# SCH_TEMT6000.net
KiCad netlist of a schematic drawn in Altium Designer
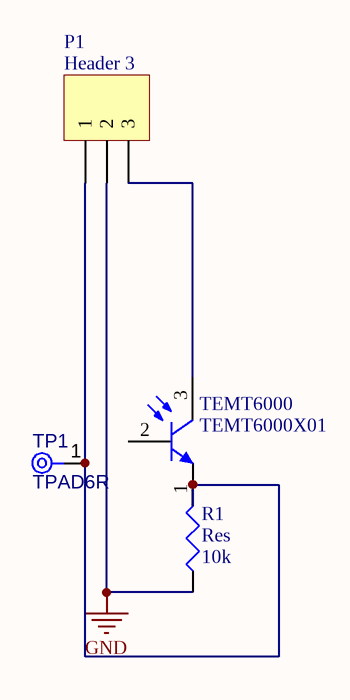
[diagram p0: SCH_TEMT6000.SchDoc]

(export (version "E")
  (design (tool "Eeschema 10.0.6"))
  (components
    (comp (ref "P1")
      (value "Header 3")
      (footprint "HDR1X3")
      (description "Header, 3-Pin")
      (fields (field (name "PUBLISHER") "Altium Limited"))
      (libsource (lib "Miscellaneous Connectors") (part "Header 3"))
    )
    (comp (ref "R1")
      (value "Res")
      (footprint "J1-0603")
      (description "Resistor")
      (fields (field (name "ALTIUM_VALUE") "10k") (field (name "PUBLISHER") "Altium Limited"))
      (libsource (lib "Miscellaneous Devices") (part "Res3"))
    )
    (comp (ref "TEMT6000")
      (value "TEMT6000X01")
      (footprint "VSIL-TEMT6000X01_V")
      (description "Ambient Light Sensor, 100 mW, -40 to 100 degC, 3-Pin SMD, RoHS, Tape and Reel")
      (fields (field (name "MANUFACTURER") "Vishay Siliconix"))
      (libsource (lib "Titouan Lasquellec") (part "PHOTO-NPN-EBC-3"))
    )
    (comp (ref "TP1")
      (value "TPAD6R")
      (footprint "TP06R")
      (description "0.6mm round")
      (libsource (lib "Titouan Lasquellec") (part "CMP-001-0001-4"))
    )
  )
  (nets
    (net (code "1") (name "GND") (class "Default")
      (node (ref "P1") (pin "2") (pinfunction "2_2") (pintype "passive"))
      (node (ref "R1") (pin "1") (pinfunction "1_1") (pintype "passive"))
    )
    (net (code "2") (name "Net-(TEMT6000-C)") (class "Default")
      (node (ref "P1") (pin "3") (pinfunction "3_3") (pintype "passive"))
      (node (ref "TEMT6000") (pin "3") (pinfunction "C_3") (pintype "passive"))
    )
    (net (code "3") (name "Net-(TEMT6000-E)") (class "Default")
      (node (ref "P1") (pin "1") (pinfunction "1_1") (pintype "passive"))
      (node (ref "R1") (pin "2") (pinfunction "2_2") (pintype "passive"))
      (node (ref "TEMT6000") (pin "1") (pinfunction "E_1") (pintype "passive"))
      (node (ref "TP1") (pin "1") (pinfunction "TP_1") (pintype "passive"))
    )
    (net (code "4") (name "unconnected-(TEMT6000-B-Pad2)") (class "Default")
      (node (ref "TEMT6000") (pin "2") (pinfunction "B_2") (pintype "passive"))
    )
  )
)
